# ti-tps61288-native-junctions.net
KiCad netlist of a schematic drawn in Altium Designer
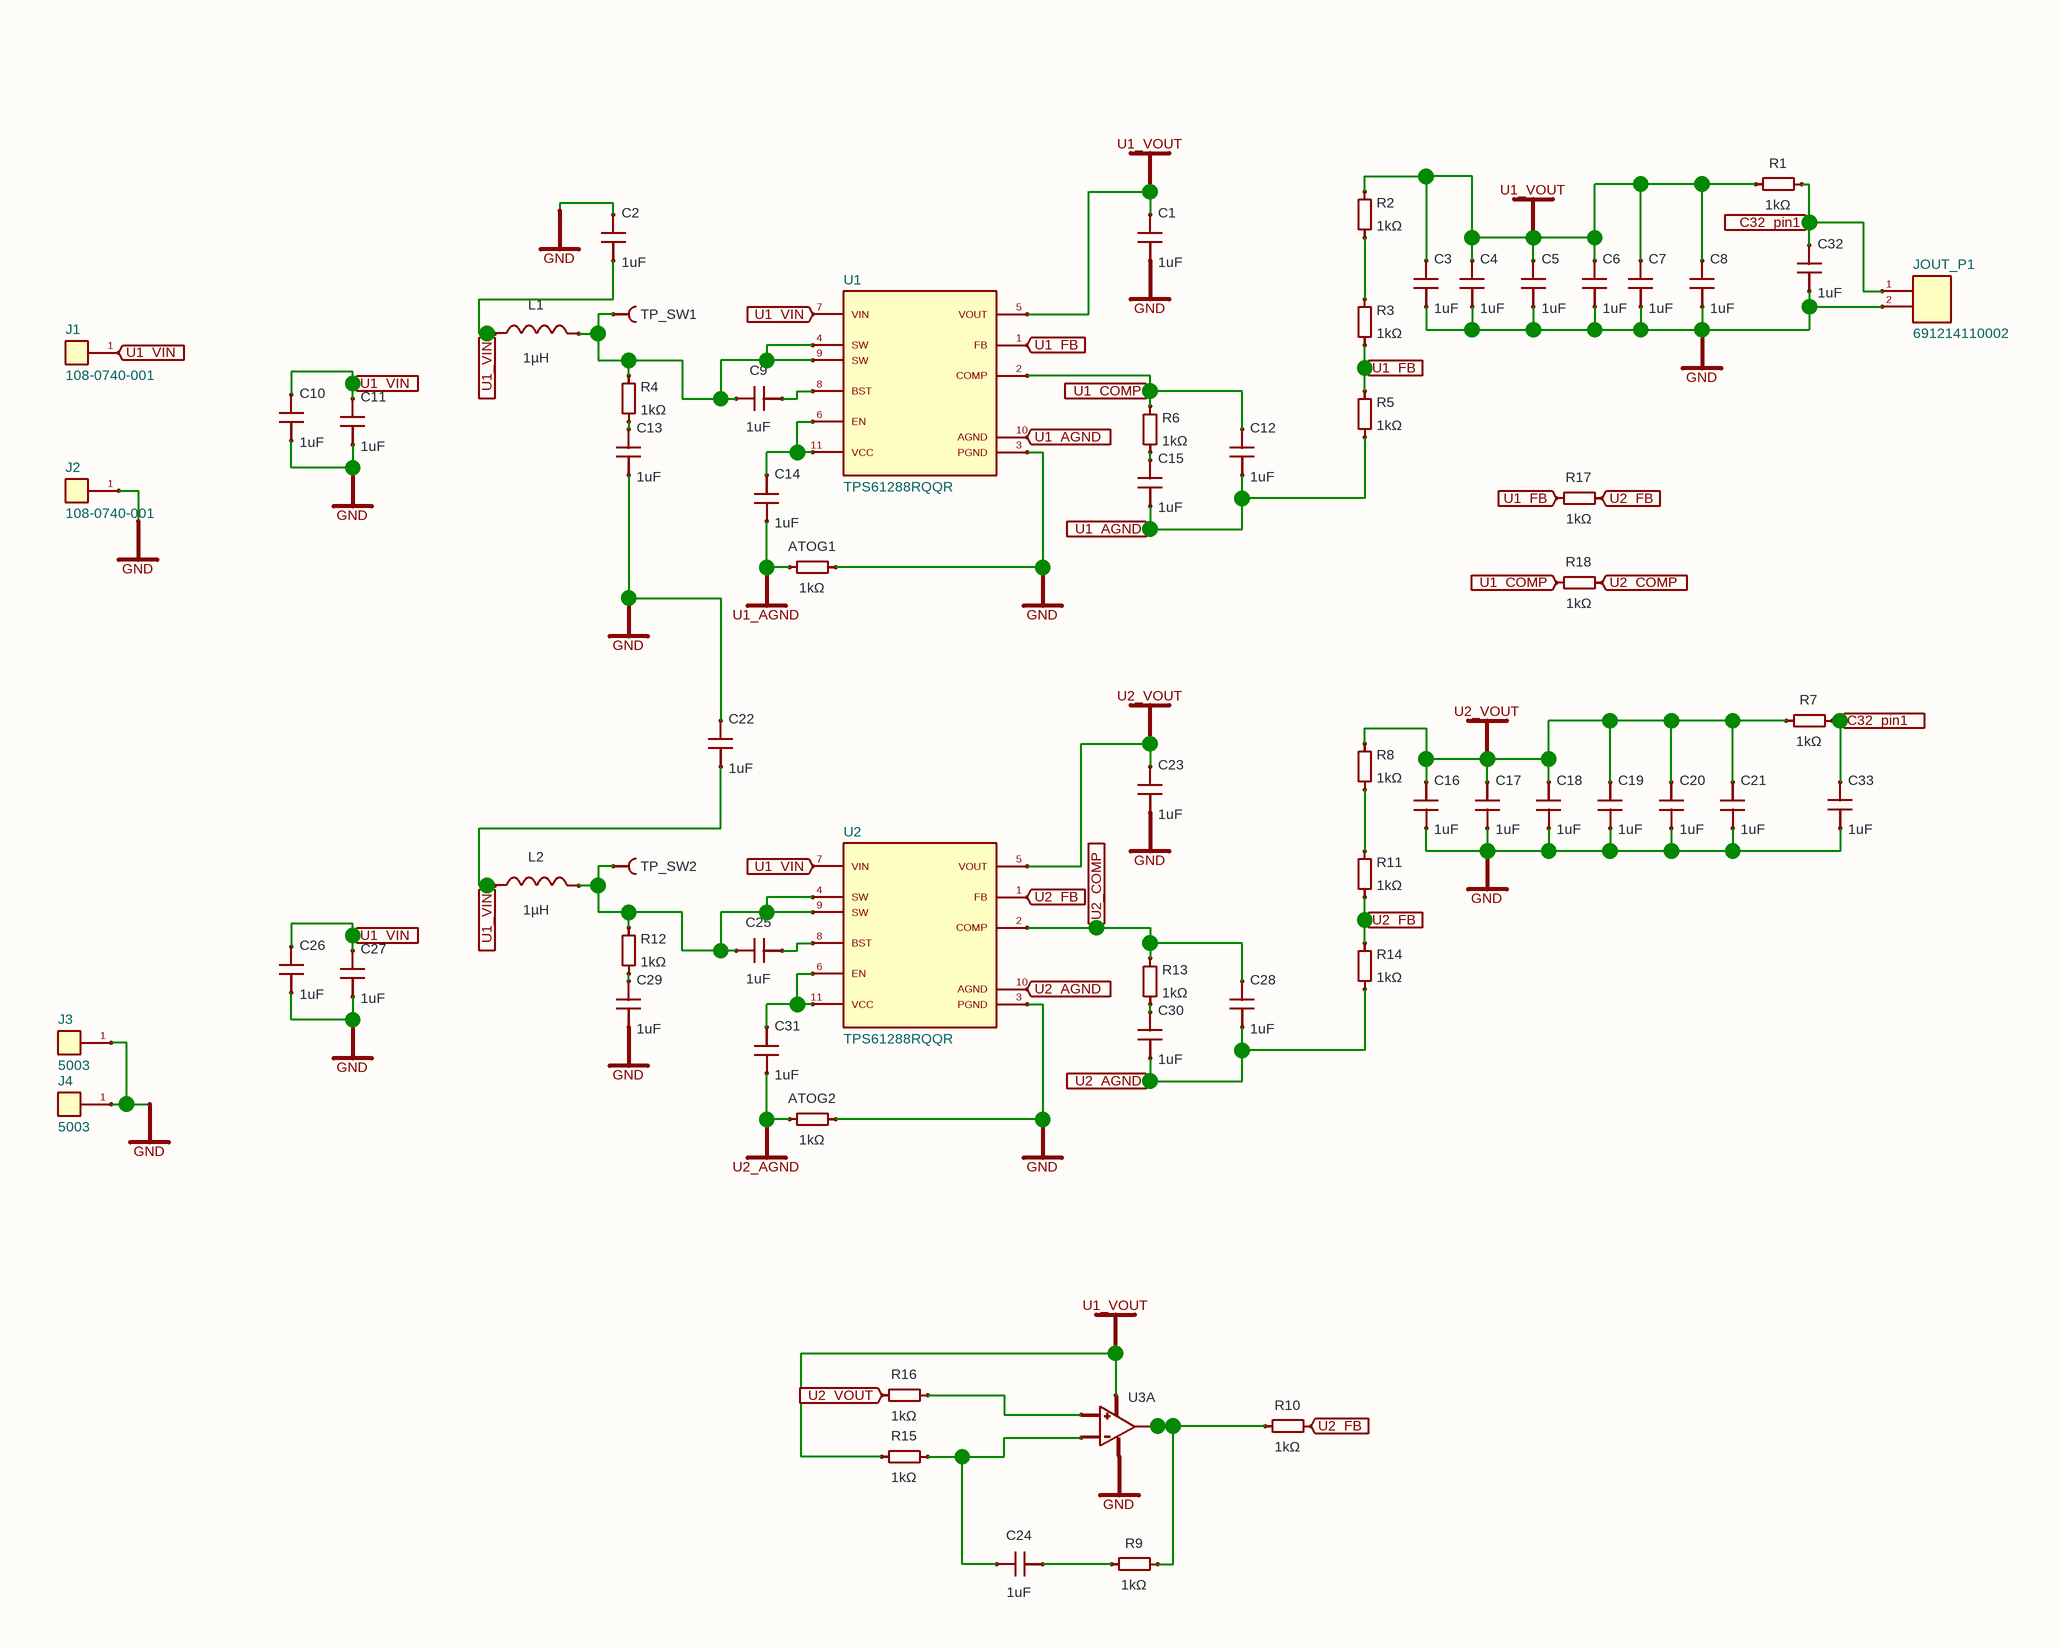
[diagram p0: ti-tps61288-native-junctions.SchDoc]

(export (version "E")
  (design (tool "Eeschema 10.0.6"))
  (components
    (comp (ref "ATOG1") (value "1kΩ") (libsource (lib "altium-import") (part "root_0_boxresistor_left_")))
    (comp (ref "ATOG2") (value "1kΩ") (libsource (lib "altium-import") (part "root_0_boxresistor_left_")))
    (comp (ref "C1") (value "1uF") (libsource (lib "") (part "root_0_capacitor_down__1")))
    (comp (ref "C2") (value "1uF") (libsource (lib "") (part "root_0_capacitor_down__1")))
    (comp (ref "C3") (value "1uF") (libsource (lib "") (part "root_0_capacitor_down__1")))
    (comp (ref "C4") (value "1uF") (libsource (lib "") (part "root_0_capacitor_down__1")))
    (comp (ref "C5") (value "1uF") (libsource (lib "") (part "root_0_capacitor_down__1")))
    (comp (ref "C6") (value "1uF") (libsource (lib "") (part "root_0_capacitor_down__1")))
    (comp (ref "C7") (value "1uF") (libsource (lib "") (part "root_0_capacitor_down__1")))
    (comp (ref "C8") (value "1uF") (libsource (lib "") (part "root_0_capacitor_down__1")))
    (comp (ref "C9") (value "1uF") (libsource (lib "altium-import") (part "root_0_capacitor_right_")))
    (comp (ref "C10") (value "1uF") (libsource (lib "altium-import") (part "root_0_capacitor_down_")))
    (comp (ref "C11") (value "1uF") (libsource (lib "") (part "root_0_capacitor_down__1")))
    (comp (ref "C12") (value "1uF") (libsource (lib "") (part "root_0_capacitor_down__1")))
    (comp (ref "C13") (value "1uF") (libsource (lib "") (part "root_0_capacitor_down__1")))
    (comp (ref "C14") (value "1uF") (libsource (lib "altium-import") (part "root_0_capacitor_up_")))
    (comp (ref "C15") (value "1uF") (libsource (lib "") (part "root_0_capacitor_down__1")))
    (comp (ref "C16") (value "1uF") (libsource (lib "altium-import") (part "root_0_capacitor_up_")))
    (comp (ref "C17") (value "1uF") (libsource (lib "altium-import") (part "root_0_capacitor_up_")))
    (comp (ref "C18") (value "1uF") (libsource (lib "altium-import") (part "root_0_capacitor_up_")))
    (comp (ref "C19") (value "1uF") (libsource (lib "altium-import") (part "root_0_capacitor_up_")))
    (comp (ref "C20") (value "1uF") (libsource (lib "altium-import") (part "root_0_capacitor_up_")))
    (comp (ref "C21") (value "1uF") (libsource (lib "altium-import") (part "root_0_capacitor_up_")))
    (comp (ref "C22") (value "1uF") (libsource (lib "") (part "root_0_capacitor_down__1")))
    (comp (ref "C23") (value "1uF") (libsource (lib "") (part "root_0_capacitor_down__1")))
    (comp (ref "C24") (value "1uF") (libsource (lib "altium-import") (part "root_0_capacitor_left_")))
    (comp (ref "C25") (value "1uF") (libsource (lib "altium-import") (part "root_0_capacitor_right_")))
    (comp (ref "C26") (value "1uF") (libsource (lib "altium-import") (part "root_0_capacitor_down_")))
    (comp (ref "C27") (value "1uF") (libsource (lib "") (part "root_0_capacitor_down__1")))
    (comp (ref "C28") (value "1uF") (libsource (lib "") (part "root_0_capacitor_down__1")))
    (comp (ref "C29") (value "1uF") (libsource (lib "") (part "root_0_capacitor_down__1")))
    (comp (ref "C30") (value "1uF") (libsource (lib "") (part "root_0_capacitor_down__1")))
    (comp (ref "C31") (value "1uF") (libsource (lib "altium-import") (part "root_0_capacitor_up_")))
    (comp (ref "C32") (value "1uF") (libsource (lib "") (part "root_0_capacitor_down__1")))
    (comp (ref "C33") (value "1uF") (libsource (lib "") (part "root_0_capacitor_down__1")))
    (comp (ref "J1") (value "~") (libsource (lib "altium-import") (part "root_0_J1_")))
    (comp (ref "J2") (value "~") (libsource (lib "altium-import") (part "root_0_J2_")))
    (comp (ref "J3") (value "~") (libsource (lib "altium-import") (part "root_0_J3_")))
    (comp (ref "J4") (value "~") (libsource (lib "altium-import") (part "root_0_J4_")))
    (comp (ref "JOUT_P1") (value "~") (libsource (lib "altium-import") (part "root_0_JOUT_P1_")))
    (comp (ref "L1") (value "1µH") (libsource (lib "altium-import") (part "root_0_inductor_right_")))
    (comp (ref "L2") (value "1µH") (libsource (lib "altium-import") (part "root_0_inductor_right_")))
    (comp (ref "R1") (value "1kΩ") (libsource (lib "altium-import") (part "root_0_boxresistor_right_")))
    (comp (ref "R2") (value "1kΩ") (libsource (lib "altium-import") (part "root_0_boxresistor_up_")))
    (comp (ref "R3") (value "1kΩ") (libsource (lib "altium-import") (part "root_0_boxresistor_up_")))
    (comp (ref "R4") (value "1kΩ") (libsource (lib "altium-import") (part "root_0_boxresistor_down_")))
    (comp (ref "R5") (value "1kΩ") (libsource (lib "altium-import") (part "root_0_boxresistor_down_")))
    (comp (ref "R6") (value "1kΩ") (libsource (lib "altium-import") (part "root_0_boxresistor_up_")))
    (comp (ref "R7") (value "1kΩ") (libsource (lib "altium-import") (part "root_0_boxresistor_right_")))
    (comp (ref "R8") (value "1kΩ") (libsource (lib "altium-import") (part "root_0_boxresistor_down_")))
    (comp (ref "R9") (value "1kΩ") (libsource (lib "altium-import") (part "root_0_boxresistor_right_")))
    (comp (ref "R10") (value "1kΩ") (libsource (lib "altium-import") (part "root_0_boxresistor_right_")))
    (comp (ref "R11") (value "1kΩ") (libsource (lib "altium-import") (part "root_0_boxresistor_up_")))
    (comp (ref "R12") (value "1kΩ") (libsource (lib "altium-import") (part "root_0_boxresistor_down_")))
    (comp (ref "R13") (value "1kΩ") (libsource (lib "altium-import") (part "root_0_boxresistor_up_")))
    (comp (ref "R14") (value "1kΩ") (libsource (lib "altium-import") (part "root_0_boxresistor_down_")))
    (comp (ref "R15") (value "1kΩ") (libsource (lib "altium-import") (part "root_0_boxresistor_right_")))
    (comp (ref "R16") (value "1kΩ") (libsource (lib "altium-import") (part "root_0_boxresistor_right_")))
    (comp (ref "R17") (value "1kΩ") (libsource (lib "altium-import") (part "root_0_boxresistor_left_")))
    (comp (ref "R18") (value "1kΩ") (libsource (lib "altium-import") (part "root_0_boxresistor_left_")))
    (comp (ref "TP_SW1") (value "~") (libsource (lib "altium-import") (part "root_0_testpoint_right_")))
    (comp (ref "TP_SW2") (value "~") (libsource (lib "altium-import") (part "root_0_testpoint_right_")))
    (comp (ref "U1") (value "~") (libsource (lib "altium-import") (part "root_0_U1_")))
    (comp (ref "U2") (value "~") (libsource (lib "altium-import") (part "root_0_U2_")))
    (comp (ref "U3A") (value "~") (libsource (lib "altium-import") (part "root_0_opamp_with_power_right_")))
  )
  (nets
    (net (code "1") (name "/C32_pin1") (class "Default")
      (node (ref "C32") (pin "1") (pinfunction "anode_1") (pintype "passive"))
      (node (ref "C33") (pin "1") (pinfunction "anode_1") (pintype "passive"))
      (node (ref "JOUT_P1") (pin "1") (pinfunction "1_1") (pintype "passive"))
      (node (ref "R1") (pin "2") (pinfunction "cathode_2") (pintype "passive"))
      (node (ref "R7") (pin "2") (pinfunction "cathode_2") (pintype "passive"))
    )
    (net (code "2") (name "/U1_COMP") (class "Default")
      (node (ref "C12") (pin "1") (pinfunction "anode_1") (pintype "passive"))
      (node (ref "R18") (pin "2") (pinfunction "cathode_2") (pintype "passive"))
      (node (ref "R6") (pin "2") (pinfunction "cathode_2") (pintype "passive"))
      (node (ref "U1") (pin "2") (pinfunction "COMP_2") (pintype "passive"))
    )
    (net (code "3") (name "/U1_FB") (class "Default")
      (node (ref "R17") (pin "2") (pinfunction "cathode_2") (pintype "passive"))
      (node (ref "R3") (pin "1") (pinfunction "anode_1") (pintype "passive"))
      (node (ref "R5") (pin "1") (pinfunction "anode_1") (pintype "passive"))
      (node (ref "U1") (pin "1") (pinfunction "FB_1") (pintype "passive"))
    )
    (net (code "4") (name "/U1_VIN") (class "Default")
      (node (ref "C10") (pin "1") (pinfunction "anode_1") (pintype "passive"))
      (node (ref "C11") (pin "1") (pinfunction "anode_1") (pintype "passive"))
      (node (ref "C2") (pin "2") (pinfunction "cathode_2") (pintype "passive"))
      (node (ref "C22") (pin "2") (pinfunction "cathode_2") (pintype "passive"))
      (node (ref "C26") (pin "1") (pinfunction "anode_1") (pintype "passive"))
      (node (ref "C27") (pin "1") (pinfunction "anode_1") (pintype "passive"))
      (node (ref "J1") (pin "1") (pinfunction "1_1") (pintype "passive"))
      (node (ref "L1") (pin "1") (pinfunction "anode_1") (pintype "passive"))
      (node (ref "L2") (pin "1") (pinfunction "anode_1") (pintype "passive"))
      (node (ref "U1") (pin "7") (pinfunction "VIN_7") (pintype "passive"))
      (node (ref "U2") (pin "7") (pinfunction "VIN_7") (pintype "passive"))
    )
    (net (code "5") (name "/U2_COMP") (class "Default")
      (node (ref "C28") (pin "1") (pinfunction "anode_1") (pintype "passive"))
      (node (ref "R13") (pin "2") (pinfunction "cathode_2") (pintype "passive"))
      (node (ref "R18") (pin "1") (pinfunction "anode_1") (pintype "passive"))
      (node (ref "U2") (pin "2") (pinfunction "COMP_2") (pintype "passive"))
    )
    (net (code "6") (name "/U2_FB") (class "Default")
      (node (ref "R10") (pin "2") (pinfunction "cathode_2") (pintype "passive"))
      (node (ref "R11") (pin "1") (pinfunction "anode_1") (pintype "passive"))
      (node (ref "R14") (pin "1") (pinfunction "anode_1") (pintype "passive"))
      (node (ref "R17") (pin "1") (pinfunction "anode_1") (pintype "passive"))
      (node (ref "U2") (pin "1") (pinfunction "FB_1") (pintype "passive"))
    )
    (net (code "7") (name "GND") (class "Default")
      (node (ref "ATOG1") (pin "1") (pinfunction "anode_1") (pintype "passive"))
      (node (ref "ATOG2") (pin "1") (pinfunction "anode_1") (pintype "passive"))
      (node (ref "C1") (pin "2") (pinfunction "cathode_2") (pintype "passive"))
      (node (ref "C10") (pin "2") (pinfunction "cathode_2") (pintype "passive"))
      (node (ref "C11") (pin "2") (pinfunction "cathode_2") (pintype "passive"))
      (node (ref "C13") (pin "2") (pinfunction "cathode_2") (pintype "passive"))
      (node (ref "C16") (pin "1") (pinfunction "anode_1") (pintype "passive"))
      (node (ref "C17") (pin "1") (pinfunction "anode_1") (pintype "passive"))
      (node (ref "C18") (pin "1") (pinfunction "anode_1") (pintype "passive"))
      (node (ref "C19") (pin "1") (pinfunction "anode_1") (pintype "passive"))
      (node (ref "C2") (pin "1") (pinfunction "anode_1") (pintype "passive"))
      (node (ref "C20") (pin "1") (pinfunction "anode_1") (pintype "passive"))
      (node (ref "C21") (pin "1") (pinfunction "anode_1") (pintype "passive"))
      (node (ref "C22") (pin "1") (pinfunction "anode_1") (pintype "passive"))
      (node (ref "C23") (pin "2") (pinfunction "cathode_2") (pintype "passive"))
      (node (ref "C26") (pin "2") (pinfunction "cathode_2") (pintype "passive"))
      (node (ref "C27") (pin "2") (pinfunction "cathode_2") (pintype "passive"))
      (node (ref "C29") (pin "2") (pinfunction "cathode_2") (pintype "passive"))
      (node (ref "C3") (pin "2") (pinfunction "cathode_2") (pintype "passive"))
      (node (ref "C32") (pin "2") (pinfunction "cathode_2") (pintype "passive"))
      (node (ref "C33") (pin "2") (pinfunction "cathode_2") (pintype "passive"))
      (node (ref "C4") (pin "2") (pinfunction "cathode_2") (pintype "passive"))
      (node (ref "C5") (pin "2") (pinfunction "cathode_2") (pintype "passive"))
      (node (ref "C6") (pin "2") (pinfunction "cathode_2") (pintype "passive"))
      (node (ref "C7") (pin "2") (pinfunction "cathode_2") (pintype "passive"))
      (node (ref "C8") (pin "2") (pinfunction "cathode_2") (pintype "passive"))
      (node (ref "J2") (pin "1") (pinfunction "1_1") (pintype "passive"))
      (node (ref "J3") (pin "1") (pinfunction "1_1") (pintype "passive"))
      (node (ref "J4") (pin "1") (pinfunction "1_1") (pintype "passive"))
      (node (ref "JOUT_P1") (pin "2") (pinfunction "2_2") (pintype "passive"))
      (node (ref "U1") (pin "3") (pinfunction "PGND_3") (pintype "passive"))
      (node (ref "U2") (pin "3") (pinfunction "PGND_3") (pintype "passive"))
      (node (ref "U3A") (pin "3") (pinfunction "V-_3") (pintype "passive"))
    )
    (net (code "8") (name "Net-(C9-neg)") (class "Default")
      (node (ref "C9") (pin "2") (pinfunction "neg_2") (pintype "passive"))
      (node (ref "U1") (pin "8") (pinfunction "BST_8") (pintype "passive"))
    )
    (net (code "9") (name "Net-(C9-pos)") (class "Default")
      (node (ref "C9") (pin "1") (pinfunction "pos_1") (pintype "passive"))
      (node (ref "L1") (pin "2") (pinfunction "cathode_2") (pintype "passive"))
      (node (ref "R4") (pin "1") (pinfunction "anode_1") (pintype "passive"))
      (node (ref "TP_SW1") (pin "1") (pinfunction "pin1_1") (pintype "passive"))
      (node (ref "U1") (pin "4") (pinfunction "SW_4") (pintype "passive"))
      (node (ref "U1") (pin "9") (pinfunction "SW_9") (pintype "passive"))
    )
    (net (code "10") (name "Net-(C13-anode)") (class "Default")
      (node (ref "C13") (pin "1") (pinfunction "anode_1") (pintype "passive"))
      (node (ref "R4") (pin "2") (pinfunction "cathode_2") (pintype "passive"))
    )
    (net (code "11") (name "Net-(C14-cathode)") (class "Default")
      (node (ref "C14") (pin "2") (pinfunction "cathode_2") (pintype "passive"))
      (node (ref "U1") (pin "11") (pinfunction "VCC_11") (pintype "passive"))
      (node (ref "U1") (pin "6") (pinfunction "EN_6") (pintype "passive"))
    )
    (net (code "12") (name "Net-(C15-anode)") (class "Default")
      (node (ref "C15") (pin "1") (pinfunction "anode_1") (pintype "passive"))
      (node (ref "R6") (pin "1") (pinfunction "anode_1") (pintype "passive"))
    )
    (net (code "13") (name "Net-(C24-neg)") (class "Default")
      (node (ref "C24") (pin "2") (pinfunction "neg_2") (pintype "passive"))
      (node (ref "R15") (pin "2") (pinfunction "cathode_2") (pintype "passive"))
      (node (ref "U3A") (pin "2") (pinfunction "inp2_2") (pintype "passive"))
    )
    (net (code "14") (name "Net-(C24-pos)") (class "Default")
      (node (ref "C24") (pin "1") (pinfunction "pos_1") (pintype "passive"))
      (node (ref "R9") (pin "1") (pinfunction "anode_1") (pintype "passive"))
    )
    (net (code "15") (name "Net-(C25-neg)") (class "Default")
      (node (ref "C25") (pin "2") (pinfunction "neg_2") (pintype "passive"))
      (node (ref "U2") (pin "8") (pinfunction "BST_8") (pintype "passive"))
    )
    (net (code "16") (name "Net-(C25-pos)") (class "Default")
      (node (ref "C25") (pin "1") (pinfunction "pos_1") (pintype "passive"))
      (node (ref "L2") (pin "2") (pinfunction "cathode_2") (pintype "passive"))
      (node (ref "R12") (pin "1") (pinfunction "anode_1") (pintype "passive"))
      (node (ref "TP_SW2") (pin "1") (pinfunction "pin1_1") (pintype "passive"))
      (node (ref "U2") (pin "4") (pinfunction "SW_4") (pintype "passive"))
      (node (ref "U2") (pin "9") (pinfunction "SW_9") (pintype "passive"))
    )
    (net (code "17") (name "Net-(C29-anode)") (class "Default")
      (node (ref "C29") (pin "1") (pinfunction "anode_1") (pintype "passive"))
      (node (ref "R12") (pin "2") (pinfunction "cathode_2") (pintype "passive"))
    )
    (net (code "18") (name "Net-(C30-anode)") (class "Default")
      (node (ref "C30") (pin "1") (pinfunction "anode_1") (pintype "passive"))
      (node (ref "R13") (pin "1") (pinfunction "anode_1") (pintype "passive"))
    )
    (net (code "19") (name "Net-(C31-cathode)") (class "Default")
      (node (ref "C31") (pin "2") (pinfunction "cathode_2") (pintype "passive"))
      (node (ref "U2") (pin "11") (pinfunction "VCC_11") (pintype "passive"))
      (node (ref "U2") (pin "6") (pinfunction "EN_6") (pintype "passive"))
    )
    (net (code "20") (name "Net-(R2-anode)") (class "Default")
      (node (ref "R2") (pin "1") (pinfunction "anode_1") (pintype "passive"))
      (node (ref "R3") (pin "2") (pinfunction "cathode_2") (pintype "passive"))
    )
    (net (code "21") (name "Net-(R10-anode)") (class "Default")
      (node (ref "R10") (pin "1") (pinfunction "anode_1") (pintype "passive"))
      (node (ref "R9") (pin "2") (pinfunction "cathode_2") (pintype "passive"))
      (node (ref "U3A") (pin "4") (pinfunction "out_4") (pintype "passive"))
    )
    (net (code "22") (name "Net-(R11-cathode)") (class "Default")
      (node (ref "R11") (pin "2") (pinfunction "cathode_2") (pintype "passive"))
      (node (ref "R8") (pin "2") (pinfunction "cathode_2") (pintype "passive"))
    )
    (net (code "23") (name "Net-(R16-cathode)") (class "Default")
      (node (ref "R16") (pin "2") (pinfunction "cathode_2") (pintype "passive"))
      (node (ref "U3A") (pin "1") (pinfunction "inp1_1") (pintype "passive"))
    )
    (net (code "24") (name "U1_AGND") (class "Default")
      (node (ref "ATOG1") (pin "2") (pinfunction "cathode_2") (pintype "passive"))
      (node (ref "C12") (pin "2") (pinfunction "cathode_2") (pintype "passive"))
      (node (ref "C14") (pin "1") (pinfunction "anode_1") (pintype "passive"))
      (node (ref "C15") (pin "2") (pinfunction "cathode_2") (pintype "passive"))
      (node (ref "R5") (pin "2") (pinfunction "cathode_2") (pintype "passive"))
      (node (ref "U1") (pin "10") (pinfunction "AGND_10") (pintype "passive"))
    )
    (net (code "25") (name "U1_VOUT") (class "Default")
      (node (ref "C1") (pin "1") (pinfunction "anode_1") (pintype "passive"))
      (node (ref "C3") (pin "1") (pinfunction "anode_1") (pintype "passive"))
      (node (ref "C4") (pin "1") (pinfunction "anode_1") (pintype "passive"))
      (node (ref "C5") (pin "1") (pinfunction "anode_1") (pintype "passive"))
      (node (ref "C6") (pin "1") (pinfunction "anode_1") (pintype "passive"))
      (node (ref "C7") (pin "1") (pinfunction "anode_1") (pintype "passive"))
      (node (ref "C8") (pin "1") (pinfunction "anode_1") (pintype "passive"))
      (node (ref "R1") (pin "1") (pinfunction "anode_1") (pintype "passive"))
      (node (ref "R15") (pin "1") (pinfunction "anode_1") (pintype "passive"))
      (node (ref "R2") (pin "2") (pinfunction "cathode_2") (pintype "passive"))
      (node (ref "U1") (pin "5") (pinfunction "VOUT_5") (pintype "passive"))
      (node (ref "U3A") (pin "5") (pinfunction "V+_5") (pintype "passive"))
    )
    (net (code "26") (name "U2_AGND") (class "Default")
      (node (ref "ATOG2") (pin "2") (pinfunction "cathode_2") (pintype "passive"))
      (node (ref "C28") (pin "2") (pinfunction "cathode_2") (pintype "passive"))
      (node (ref "C30") (pin "2") (pinfunction "cathode_2") (pintype "passive"))
      (node (ref "C31") (pin "1") (pinfunction "anode_1") (pintype "passive"))
      (node (ref "R14") (pin "2") (pinfunction "cathode_2") (pintype "passive"))
      (node (ref "U2") (pin "10") (pinfunction "AGND_10") (pintype "passive"))
    )
    (net (code "27") (name "U2_VOUT") (class "Default")
      (node (ref "C16") (pin "2") (pinfunction "cathode_2") (pintype "passive"))
      (node (ref "C17") (pin "2") (pinfunction "cathode_2") (pintype "passive"))
      (node (ref "C18") (pin "2") (pinfunction "cathode_2") (pintype "passive"))
      (node (ref "C19") (pin "2") (pinfunction "cathode_2") (pintype "passive"))
      (node (ref "C20") (pin "2") (pinfunction "cathode_2") (pintype "passive"))
      (node (ref "C21") (pin "2") (pinfunction "cathode_2") (pintype "passive"))
      (node (ref "C23") (pin "1") (pinfunction "anode_1") (pintype "passive"))
      (node (ref "R16") (pin "1") (pinfunction "anode_1") (pintype "passive"))
      (node (ref "R7") (pin "1") (pinfunction "anode_1") (pintype "passive"))
      (node (ref "R8") (pin "1") (pinfunction "anode_1") (pintype "passive"))
      (node (ref "U2") (pin "5") (pinfunction "VOUT_5") (pintype "passive"))
    )
  )
)
